# power.net
KiCad netlist of a schematic drawn in Altium Designer
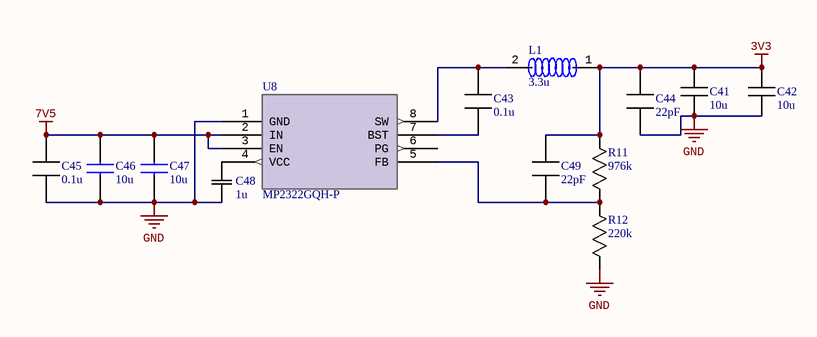
[diagram p0: power.SchDoc]

(export (version "E")
  (design (tool "Eeschema 10.0.6"))
  (components
    (comp (ref "C41")
      (value "10u")
      (footprint "C0603C911F5GACTU:CAPC17595_87N_KEM")
      (description "CC0603KRX5R5BB106 10 uF, 10%, 6.3 VDC, X5R")
      (fields (field (name "MANUFACTURER_PART_NUMBER") "CC0603KRX5R5BB106"))
      (libsource (lib "CC0603KRX5R5BB106") (part "CC0603KRX5R5BB106"))
    )
    (comp (ref "C42")
      (value "10u")
      (footprint "C0603C911F5GACTU:CAPC17595_87N_KEM")
      (description "CC0603KRX5R5BB106 10 uF, 10%, 6.3 VDC, X5R")
      (fields (field (name "MANUFACTURER_PART_NUMBER") "CC0603KRX5R5BB106"))
      (libsource (lib "CC0603KRX5R5BB106") (part "CC0603KRX5R5BB106"))
    )
    (comp (ref "C43")
      (value "0.1u")
      (footprint "C0603C911F5GACTU:CAPC17595_87N_KEM")
      (description "50V X7R 0603")
      (fields (field (name "MANUFACTURER_PART_NUMBER") "CC0603KRX7R9BB104"))
      (libsource (lib "CC0603KRX7R9BB104") (part "CC0603KRX7R9BB104"))
    )
    (comp (ref "C44")
      (value "22pF")
      (footprint "C0603C911F5GACTU:CAPC17595_87N_KEM")
      (description "22pF C0G, 22 pF, 5%, 100 VDC, C0G")
      (fields (field (name "MANUFACTURER_PART_NUMBER") "C0603C220J1GACTU"))
      (libsource (lib "CC0603KRX7R9BB104") (part "C0603C220J1GACTU"))
    )
    (comp (ref "C45")
      (value "0.1u")
      (footprint "C0603C911F5GACTU:CAPC17595_87N_KEM")
      (description "50V X7R 0603")
      (fields (field (name "MANUFACTURER_PART_NUMBER") "CC0603KRX7R9BB104"))
      (libsource (lib "CC0603KRX7R9BB104") (part "CC0603KRX7R9BB104"))
    )
    (comp (ref "C46")
      (value "10u")
      (footprint "CAPC2012X145N:CAPC2012X145N")
      (fields
        (field (name "MANUFACTURER_PART_NUMBER") "CC0805KKX5R8BB106")
        (field (name "MOUSER PART NUMBER") "603-CC805KKX5R8BB106")
      )
      (libsource (lib "CC0805KKX5R8BB106") (part "CC0805KKX5R8BB106"))
    )
    (comp (ref "C47")
      (value "10u")
      (footprint "CAPC2012X145N:CAPC2012X145N")
      (fields
        (field (name "MANUFACTURER_PART_NUMBER") "CC0805KKX5R8BB106")
        (field (name "MOUSER PART NUMBER") "603-CC805KKX5R8BB106")
      )
      (libsource (lib "CC0805KKX5R8BB106") (part "CC0805KKX5R8BB106"))
    )
    (comp (ref "C48")
      (value "1u")
      (footprint "CAP_CC0201_YAG")
      (description "No Description Available")
      (fields
        (field (name "MANUFACTURER_PART_NUMBER") "CC0201MRX5R5BB105")
        (field (name "COPYRIGHT") "Copyright (C) 2025 Ultra Librarian. All rights reserved.")
      )
      (libsource (lib "Ben Cheng") (part "CC0201MRX5R5BB105"))
    )
    (comp (ref "C49")
      (value "22pF")
      (footprint "C0603C911F5GACTU:CAPC17595_87N_KEM")
      (description "22pF C0G, 22 pF, 5%, 100 VDC, C0G")
      (fields (field (name "MANUFACTURER_PART_NUMBER") "C0603C220J1GACTU"))
      (libsource (lib "CC0603KRX7R9BB104") (part "C0603C220J1GACTU"))
    )
    (comp (ref "L1")
      (value "3.3u")
      (footprint "Coil MPS:MPL-AT2512-XXX")
      (description "Low-Profile Molded Inductor 3.3µH")
      (fields (field (name "MANUFACTURER_PART_NUMBER") "MPL-AT2512-3R3"))
      (libsource (lib "MPL-AT2512-3R3") (part "MPL-AT2512-3R3"))
    )
    (comp (ref "R11")
      (value "976k")
      (footprint "ERA-3AEB153V:RC0603N_PAN")
      (fields (field (name "MANUFACTURER_PART_NUMBER") "RT0603BRD07976KL"))
      (libsource (lib "ERA-3AEB153V") (part "RT0603BRD07976KL"))
    )
    (comp (ref "R12")
      (value "220k")
      (footprint "ERA-3AEB153V:RC0603N_PAN")
      (fields (field (name "MANUFACTURER_PART_NUMBER") "RT0603BRD07220KL"))
      (libsource (lib "ERA-3AEB153V") (part "RT0603BRD07220KL"))
    )
    (comp (ref "U8")
      (value "MP2322GQH-P")
      (footprint "MP2322GQH-P:QFN-8_1p5MMx2MM_MNP")
      (description "1A 3V to 22V 5渭A IQ Synchronous Step-Down Converter in a QFN-8 (1.5mmx2mm) Package")
      (fields (field (name "COPYRIGHT") "Copyright (C) 2025 Ultra Librarian. All rights reserved."))
      (libsource (lib "MP2322GQH-P") (part "MP2322GQH-P"))
    )
  )
  (nets
    (net (code "1") (name "3V3") (class "Default")
      (node (ref "C41") (pin "2") (pintype "passive"))
      (node (ref "C42") (pin "2") (pintype "passive"))
      (node (ref "C44") (pin "1") (pintype "passive"))
      (node (ref "C49") (pin "1") (pintype "passive"))
      (node (ref "L1") (pin "1") (pintype "passive"))
      (node (ref "R11") (pin "1") (pintype "passive"))
    )
    (net (code "2") (name "7V5") (class "Default")
      (node (ref "C45") (pin "2") (pintype "passive"))
      (node (ref "C46") (pin "2") (pinfunction "2_2") (pintype "passive"))
      (node (ref "C47") (pin "2") (pinfunction "2_2") (pintype "passive"))
      (node (ref "U8") (pin "2") (pinfunction "IN_2") (pintype "power_in"))
      (node (ref "U8") (pin "3") (pinfunction "EN_3") (pintype "passive"))
    )
    (net (code "3") (name "GND") (class "Default")
      (node (ref "C41") (pin "1") (pintype "passive"))
      (node (ref "C42") (pin "1") (pintype "passive"))
      (node (ref "C44") (pin "2") (pintype "passive"))
      (node (ref "C45") (pin "1") (pintype "passive"))
      (node (ref "C46") (pin "1") (pinfunction "1_1") (pintype "passive"))
      (node (ref "C47") (pin "1") (pinfunction "1_1") (pintype "passive"))
      (node (ref "C48") (pin "1") (pinfunction "1_1") (pintype "passive"))
      (node (ref "R12") (pin "2") (pintype "passive"))
      (node (ref "U8") (pin "1") (pinfunction "GND_1") (pintype "power_in"))
    )
    (net (code "4") (name "Net-(U8-BST)") (class "Default")
      (node (ref "C43") (pin "2") (pintype "passive"))
      (node (ref "U8") (pin "7") (pinfunction "BST_7") (pintype "passive"))
    )
    (net (code "5") (name "Net-(U8-FB)") (class "Default")
      (node (ref "C49") (pin "2") (pintype "passive"))
      (node (ref "R11") (pin "2") (pintype "passive"))
      (node (ref "R12") (pin "1") (pintype "passive"))
      (node (ref "U8") (pin "5") (pinfunction "FB_5") (pintype "passive"))
    )
    (net (code "6") (name "Net-(U8-SW)") (class "Default")
      (node (ref "C43") (pin "1") (pintype "passive"))
      (node (ref "L1") (pin "2") (pintype "passive"))
      (node (ref "U8") (pin "8") (pinfunction "SW_8") (pintype "output"))
    )
    (net (code "7") (name "Net-(U8-VCC)") (class "Default")
      (node (ref "C48") (pin "2") (pinfunction "2_2") (pintype "passive"))
      (node (ref "U8") (pin "4") (pinfunction "VCC_4") (pintype "output"))
    )
    (net (code "8") (name "unconnected-(U8-PG-Pad6)") (class "Default")
      (node (ref "U8") (pin "6") (pinfunction "PG_6") (pintype "output"))
    )
  )
)
